# McuSupply.net
KiCad netlist of a schematic drawn in Altium Designer
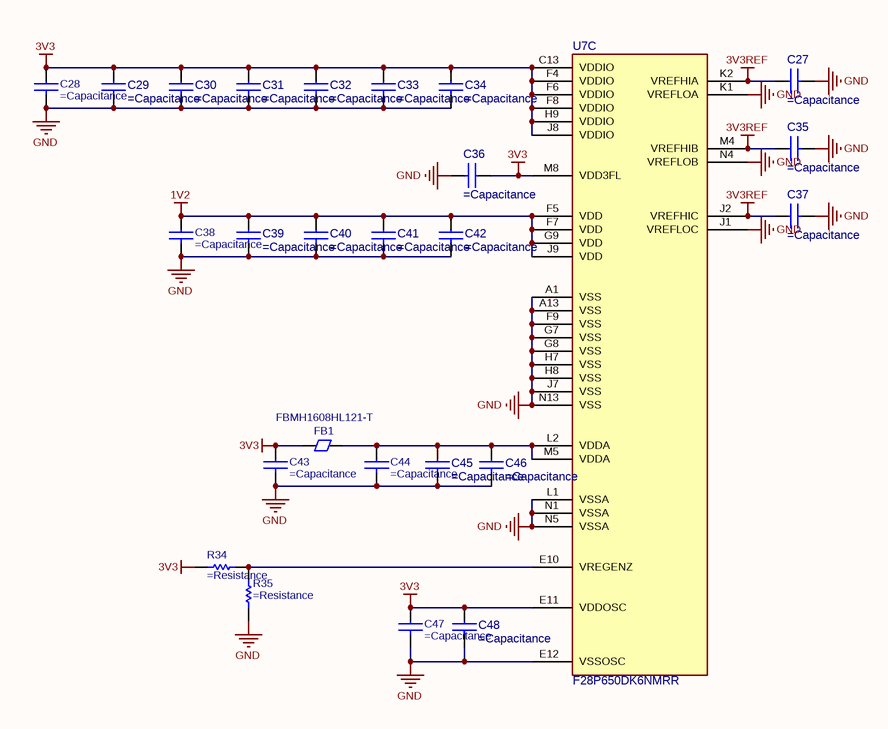
[diagram p0: McuSupply.SchDoc]

(export (version "E")
  (design (tool "Eeschema 10.0.6"))
  (components
    (comp (ref "C27")
      (value "~")
      (footprint "C0402")
      (description "CAP CER 0.1UF 50V X7R 0402")
      (fields
        (field (name "MANUFACTURER") "Walsin Technologies")
        (field (name "MANUFACTURER PART NUMBER") "0402B104K500CT")
      )
      (libsource (lib "Capacitors") (part "CAP0402-0.1uF-50V"))
    )
    (comp (ref "C28")
      (value "~")
      (footprint "C0603")
      (description "CAP CER 10UF 10V X7R 0603")
      (fields
        (field (name "MANUFACTURER") "Murata")
        (field (name "MANUFACTURER PART NUMBER") "GRM188Z71A106KA73D")
      )
      (libsource (lib "Capacitors") (part "CAP0603-10uF-10V"))
    )
    (comp (ref "C29")
      (value "~")
      (footprint "C0402")
      (description "CAP CER 0.1UF 50V X7R 0402")
      (fields
        (field (name "MANUFACTURER") "Walsin Technologies")
        (field (name "MANUFACTURER PART NUMBER") "0402B104K500CT")
      )
      (libsource (lib "Capacitors") (part "CAP0402-0.1uF-50V"))
    )
    (comp (ref "C30")
      (value "~")
      (footprint "C0402")
      (description "CAP CER 0.1UF 50V X7R 0402")
      (fields
        (field (name "MANUFACTURER") "Walsin Technologies")
        (field (name "MANUFACTURER PART NUMBER") "0402B104K500CT")
      )
      (libsource (lib "Capacitors") (part "CAP0402-0.1uF-50V"))
    )
    (comp (ref "C31")
      (value "~")
      (footprint "C0402")
      (description "CAP CER 0.1UF 50V X7R 0402")
      (fields
        (field (name "MANUFACTURER") "Walsin Technologies")
        (field (name "MANUFACTURER PART NUMBER") "0402B104K500CT")
      )
      (libsource (lib "Capacitors") (part "CAP0402-0.1uF-50V"))
    )
    (comp (ref "C32")
      (value "~")
      (footprint "C0402")
      (description "CAP CER 0.1UF 50V X7R 0402")
      (fields
        (field (name "MANUFACTURER") "Walsin Technologies")
        (field (name "MANUFACTURER PART NUMBER") "0402B104K500CT")
      )
      (libsource (lib "Capacitors") (part "CAP0402-0.1uF-50V"))
    )
    (comp (ref "C33")
      (value "~")
      (footprint "C0402")
      (description "CAP CER 0.1UF 50V X7R 0402")
      (fields
        (field (name "MANUFACTURER") "Walsin Technologies")
        (field (name "MANUFACTURER PART NUMBER") "0402B104K500CT")
      )
      (libsource (lib "Capacitors") (part "CAP0402-0.1uF-50V"))
    )
    (comp (ref "C34")
      (value "~")
      (footprint "C0402")
      (description "CAP CER 0.1UF 50V X7R 0402")
      (fields
        (field (name "MANUFACTURER") "Walsin Technologies")
        (field (name "MANUFACTURER PART NUMBER") "0402B104K500CT")
      )
      (libsource (lib "Capacitors") (part "CAP0402-0.1uF-50V"))
    )
    (comp (ref "C35")
      (value "~")
      (footprint "C0402")
      (description "CAP CER 0.1UF 50V X7R 0402")
      (fields
        (field (name "MANUFACTURER") "Walsin Technologies")
        (field (name "MANUFACTURER PART NUMBER") "0402B104K500CT")
      )
      (libsource (lib "Capacitors") (part "CAP0402-0.1uF-50V"))
    )
    (comp (ref "C36")
      (value "~")
      (footprint "C0402")
      (description "CAP CER 0.1UF 50V X7R 0402")
      (fields
        (field (name "MANUFACTURER") "Walsin Technologies")
        (field (name "MANUFACTURER PART NUMBER") "0402B104K500CT")
      )
      (libsource (lib "Capacitors") (part "CAP0402-0.1uF-50V"))
    )
    (comp (ref "C37")
      (value "~")
      (footprint "C0402")
      (description "CAP CER 0.1UF 50V X7R 0402")
      (fields
        (field (name "MANUFACTURER") "Walsin Technologies")
        (field (name "MANUFACTURER PART NUMBER") "0402B104K500CT")
      )
      (libsource (lib "Capacitors") (part "CAP0402-0.1uF-50V"))
    )
    (comp (ref "C38")
      (value "~")
      (footprint "C0603")
      (description "CAP CER 10UF 10V X7R 0603")
      (fields
        (field (name "MANUFACTURER") "Murata")
        (field (name "MANUFACTURER PART NUMBER") "GRM188Z71A106KA73D")
      )
      (libsource (lib "Capacitors") (part "CAP0603-10uF-10V"))
    )
    (comp (ref "C39")
      (value "~")
      (footprint "C0402")
      (description "CAP CER 0.1UF 50V X7R 0402")
      (fields
        (field (name "MANUFACTURER") "Walsin Technologies")
        (field (name "MANUFACTURER PART NUMBER") "0402B104K500CT")
      )
      (libsource (lib "Capacitors") (part "CAP0402-0.1uF-50V"))
    )
    (comp (ref "C40")
      (value "~")
      (footprint "C0402")
      (description "CAP CER 0.1UF 50V X7R 0402")
      (fields
        (field (name "MANUFACTURER") "Walsin Technologies")
        (field (name "MANUFACTURER PART NUMBER") "0402B104K500CT")
      )
      (libsource (lib "Capacitors") (part "CAP0402-0.1uF-50V"))
    )
    (comp (ref "C41")
      (value "~")
      (footprint "C0402")
      (description "CAP CER 0.1UF 50V X7R 0402")
      (fields
        (field (name "MANUFACTURER") "Walsin Technologies")
        (field (name "MANUFACTURER PART NUMBER") "0402B104K500CT")
      )
      (libsource (lib "Capacitors") (part "CAP0402-0.1uF-50V"))
    )
    (comp (ref "C42")
      (value "~")
      (footprint "C0402")
      (description "CAP CER 0.1UF 50V X7R 0402")
      (fields
        (field (name "MANUFACTURER") "Walsin Technologies")
        (field (name "MANUFACTURER PART NUMBER") "0402B104K500CT")
      )
      (libsource (lib "Capacitors") (part "CAP0402-0.1uF-50V"))
    )
    (comp (ref "C43")
      (value "~")
      (footprint "C0603")
      (description "CAP CER 10UF 10V X7R 0603")
      (fields
        (field (name "MANUFACTURER") "Murata")
        (field (name "MANUFACTURER PART NUMBER") "GRM188Z71A106KA73D")
      )
      (libsource (lib "Capacitors") (part "CAP0603-10uF-10V"))
    )
    (comp (ref "C44")
      (value "~")
      (footprint "C0603")
      (description "CAP CER 10UF 10V X7R 0603")
      (fields
        (field (name "MANUFACTURER") "Murata")
        (field (name "MANUFACTURER PART NUMBER") "GRM188Z71A106KA73D")
      )
      (libsource (lib "Capacitors") (part "CAP0603-10uF-10V"))
    )
    (comp (ref "C45")
      (value "~")
      (footprint "C0402")
      (description "CAP CER 0.1UF 50V X7R 0402")
      (fields
        (field (name "MANUFACTURER") "Walsin Technologies")
        (field (name "MANUFACTURER PART NUMBER") "0402B104K500CT")
      )
      (libsource (lib "Capacitors") (part "CAP0402-0.1uF-50V"))
    )
    (comp (ref "C46")
      (value "~")
      (footprint "C0402")
      (description "CAP CER 0.1UF 50V X7R 0402")
      (fields
        (field (name "MANUFACTURER") "Walsin Technologies")
        (field (name "MANUFACTURER PART NUMBER") "0402B104K500CT")
      )
      (libsource (lib "Capacitors") (part "CAP0402-0.1uF-50V"))
    )
    (comp (ref "C47")
      (value "~")
      (footprint "C0603")
      (description "CAP CER 10UF 10V X7R 0603")
      (fields
        (field (name "MANUFACTURER") "Murata")
        (field (name "MANUFACTURER PART NUMBER") "GRM188Z71A106KA73D")
      )
      (libsource (lib "Capacitors") (part "CAP0603-10uF-10V"))
    )
    (comp (ref "C48")
      (value "~")
      (footprint "C0402")
      (description "CAP CER 0.1UF 50V X7R 0402")
      (fields
        (field (name "MANUFACTURER") "Walsin Technologies")
        (field (name "MANUFACTURER PART NUMBER") "0402B104K500CT")
      )
      (libsource (lib "Capacitors") (part "CAP0402-0.1uF-50V"))
    )
    (comp (ref "FB1")
      (value "FBMH1608HL121-T")
      (footprint "FB0603")
      (description "FERRITE BEAD 120 OHM 0603 1LN")
      (fields (field (name "MANUFACTURER") "Taiyo Yuden"))
      (libsource (lib "Inductors") (part "FBMH1608HL121-T"))
    )
    (comp (ref "R34")
      (value "~")
      (footprint "R0402")
      (description "Res Thick Film 0402 10K Ohm 1% 0.063W(1/16W) ±100ppm/C Pad SMD T/R Automotive AEC-Q200")
      (fields
        (field (name "MANUFACTURER") "Vishay")
        (field (name "MANUFACTURER PART NUMBER") "CRCW040210K0FKEE")
      )
      (libsource (lib "Resistors") (part "RES0402-10k-1%"))
    )
    (comp (ref "R35")
      (value "~")
      (footprint "R0402")
      (description "Res Thick Film 0402 10K Ohm 1% 0.063W(1/16W) ±100ppm/C Pad SMD T/R Automotive AEC-Q200")
      (fields
        (field (name "MANUFACTURER") "Vishay")
        (field (name "MANUFACTURER PART NUMBER") "CRCW040210K0FKEE")
      )
      (libsource (lib "Resistors") (part "RES0402-10k-1%"))
    )
    (comp (ref "U7")
      (value "F28P650DK6NMRR")
      (footprint "IC:NFBGA169")
      (fields (field (name "MANUFACTURER") "Texas Instruments"))
      (libsource (lib "IC") (part "F28P650DK6NMRR_1"))
    )
  )
  (nets
    (net (code "1") (name "1V2") (class "Default")
      (node (ref "C38") (pin "1") (pinfunction "1_1") (pintype "passive"))
      (node (ref "C39") (pin "1") (pinfunction "1_1") (pintype "passive"))
      (node (ref "C40") (pin "1") (pinfunction "1_1") (pintype "passive"))
      (node (ref "C41") (pin "1") (pinfunction "1_1") (pintype "passive"))
      (node (ref "C42") (pin "1") (pinfunction "1_1") (pintype "passive"))
      (node (ref "U7") (pin "F5") (pinfunction "VDD_F5") (pintype "passive"))
      (node (ref "U7") (pin "F7") (pinfunction "VDD_F7") (pintype "passive"))
      (node (ref "U7") (pin "G9") (pinfunction "VDD_G9") (pintype "passive"))
      (node (ref "U7") (pin "J9") (pinfunction "VDD_J9") (pintype "passive"))
    )
    (net (code "2") (name "3V3") (class "Default")
      (node (ref "C28") (pin "1") (pinfunction "1_1") (pintype "passive"))
      (node (ref "C29") (pin "1") (pinfunction "1_1") (pintype "passive"))
      (node (ref "C30") (pin "1") (pinfunction "1_1") (pintype "passive"))
      (node (ref "C31") (pin "1") (pinfunction "1_1") (pintype "passive"))
      (node (ref "C32") (pin "1") (pinfunction "1_1") (pintype "passive"))
      (node (ref "C33") (pin "1") (pinfunction "1_1") (pintype "passive"))
      (node (ref "C34") (pin "1") (pinfunction "1_1") (pintype "passive"))
      (node (ref "C36") (pin "1") (pinfunction "1_1") (pintype "passive"))
      (node (ref "C43") (pin "1") (pinfunction "1_1") (pintype "passive"))
      (node (ref "C47") (pin "1") (pinfunction "1_1") (pintype "passive"))
      (node (ref "C48") (pin "1") (pinfunction "1_1") (pintype "passive"))
      (node (ref "FB1") (pin "1") (pinfunction "1_1") (pintype "passive"))
      (node (ref "R34") (pin "2") (pinfunction "2_2") (pintype "passive"))
      (node (ref "U7") (pin "C13") (pinfunction "VDDIO_C13") (pintype "passive"))
      (node (ref "U7") (pin "E11") (pinfunction "VDDOSC_E11") (pintype "passive"))
      (node (ref "U7") (pin "F4") (pinfunction "VDDIO_F4") (pintype "passive"))
      (node (ref "U7") (pin "F6") (pinfunction "VDDIO_F6") (pintype "passive"))
      (node (ref "U7") (pin "F8") (pinfunction "VDDIO_F8") (pintype "passive"))
      (node (ref "U7") (pin "H9") (pinfunction "VDDIO_H9") (pintype "passive"))
      (node (ref "U7") (pin "J8") (pinfunction "VDDIO_J8") (pintype "passive"))
      (node (ref "U7") (pin "M8") (pinfunction "VDD3FL_M8") (pintype "passive"))
    )
    (net (code "3") (name "3V3REF") (class "Default")
      (node (ref "C27") (pin "1") (pinfunction "1_1") (pintype "passive"))
      (node (ref "C35") (pin "1") (pinfunction "1_1") (pintype "passive"))
      (node (ref "C37") (pin "1") (pinfunction "1_1") (pintype "passive"))
      (node (ref "U7") (pin "J2") (pinfunction "VREFHIC_J2") (pintype "passive"))
      (node (ref "U7") (pin "K2") (pinfunction "VREFHIA_K2") (pintype "passive"))
      (node (ref "U7") (pin "M4") (pinfunction "VREFHIB_M4") (pintype "passive"))
    )
    (net (code "4") (name "GND") (class "Default")
      (node (ref "C27") (pin "2") (pinfunction "2_2") (pintype "passive"))
      (node (ref "C28") (pin "2") (pinfunction "2_2") (pintype "passive"))
      (node (ref "C29") (pin "2") (pinfunction "2_2") (pintype "passive"))
      (node (ref "C30") (pin "2") (pinfunction "2_2") (pintype "passive"))
      (node (ref "C31") (pin "2") (pinfunction "2_2") (pintype "passive"))
      (node (ref "C32") (pin "2") (pinfunction "2_2") (pintype "passive"))
      (node (ref "C33") (pin "2") (pinfunction "2_2") (pintype "passive"))
      (node (ref "C34") (pin "2") (pinfunction "2_2") (pintype "passive"))
      (node (ref "C35") (pin "2") (pinfunction "2_2") (pintype "passive"))
      (node (ref "C36") (pin "2") (pinfunction "2_2") (pintype "passive"))
      (node (ref "C37") (pin "2") (pinfunction "2_2") (pintype "passive"))
      (node (ref "C38") (pin "2") (pinfunction "2_2") (pintype "passive"))
      (node (ref "C39") (pin "2") (pinfunction "2_2") (pintype "passive"))
      (node (ref "C40") (pin "2") (pinfunction "2_2") (pintype "passive"))
      (node (ref "C41") (pin "2") (pinfunction "2_2") (pintype "passive"))
      (node (ref "C42") (pin "2") (pinfunction "2_2") (pintype "passive"))
      (node (ref "C43") (pin "2") (pinfunction "2_2") (pintype "passive"))
      (node (ref "C44") (pin "2") (pinfunction "2_2") (pintype "passive"))
      (node (ref "C45") (pin "2") (pinfunction "2_2") (pintype "passive"))
      (node (ref "C46") (pin "2") (pinfunction "2_2") (pintype "passive"))
      (node (ref "C47") (pin "2") (pinfunction "2_2") (pintype "passive"))
      (node (ref "C48") (pin "2") (pinfunction "2_2") (pintype "passive"))
      (node (ref "R35") (pin "1") (pinfunction "1_1") (pintype "passive"))
      (node (ref "U7") (pin "A1") (pinfunction "VSS_A1") (pintype "passive"))
      (node (ref "U7") (pin "A13") (pinfunction "VSS_A13") (pintype "passive"))
      (node (ref "U7") (pin "E12") (pinfunction "VSSOSC_E12") (pintype "passive"))
      (node (ref "U7") (pin "F9") (pinfunction "VSS_F9") (pintype "passive"))
      (node (ref "U7") (pin "G7") (pinfunction "VSS_G7") (pintype "passive"))
      (node (ref "U7") (pin "G8") (pinfunction "VSS_G8") (pintype "passive"))
      (node (ref "U7") (pin "H7") (pinfunction "VSS_H7") (pintype "passive"))
      (node (ref "U7") (pin "H8") (pinfunction "VSS_H8") (pintype "passive"))
      (node (ref "U7") (pin "J1") (pinfunction "VREFLOC_J1") (pintype "passive"))
      (node (ref "U7") (pin "J7") (pinfunction "VSS_J7") (pintype "passive"))
      (node (ref "U7") (pin "K1") (pinfunction "VREFLOA_K1") (pintype "passive"))
      (node (ref "U7") (pin "L1") (pinfunction "VSSA_L1") (pintype "passive"))
      (node (ref "U7") (pin "N1") (pinfunction "VSSA_N1") (pintype "passive"))
      (node (ref "U7") (pin "N13") (pinfunction "VSS_N13") (pintype "passive"))
      (node (ref "U7") (pin "N4") (pinfunction "VREFLOB_N4") (pintype "passive"))
      (node (ref "U7") (pin "N5") (pinfunction "VSSA_N5") (pintype "passive"))
    )
    (net (code "5") (name "Net-(C44-Pad1)") (class "Default")
      (node (ref "C44") (pin "1") (pinfunction "1_1") (pintype "passive"))
      (node (ref "C45") (pin "1") (pinfunction "1_1") (pintype "passive"))
      (node (ref "C46") (pin "1") (pinfunction "1_1") (pintype "passive"))
      (node (ref "FB1") (pin "2") (pinfunction "2_2") (pintype "passive"))
      (node (ref "U7") (pin "L2") (pinfunction "VDDA_L2") (pintype "passive"))
      (node (ref "U7") (pin "M5") (pinfunction "VDDA_M5") (pintype "passive"))
    )
    (net (code "6") (name "Net-(U7C-VREGENZ)") (class "Default")
      (node (ref "R34") (pin "1") (pinfunction "1_1") (pintype "passive"))
      (node (ref "R35") (pin "2") (pinfunction "2_2") (pintype "passive"))
      (node (ref "U7") (pin "E10") (pinfunction "VREGENZ_E10") (pintype "passive"))
    )
  )
)
